# 433_RX.net
KiCad netlist of a schematic drawn in Altium Designer
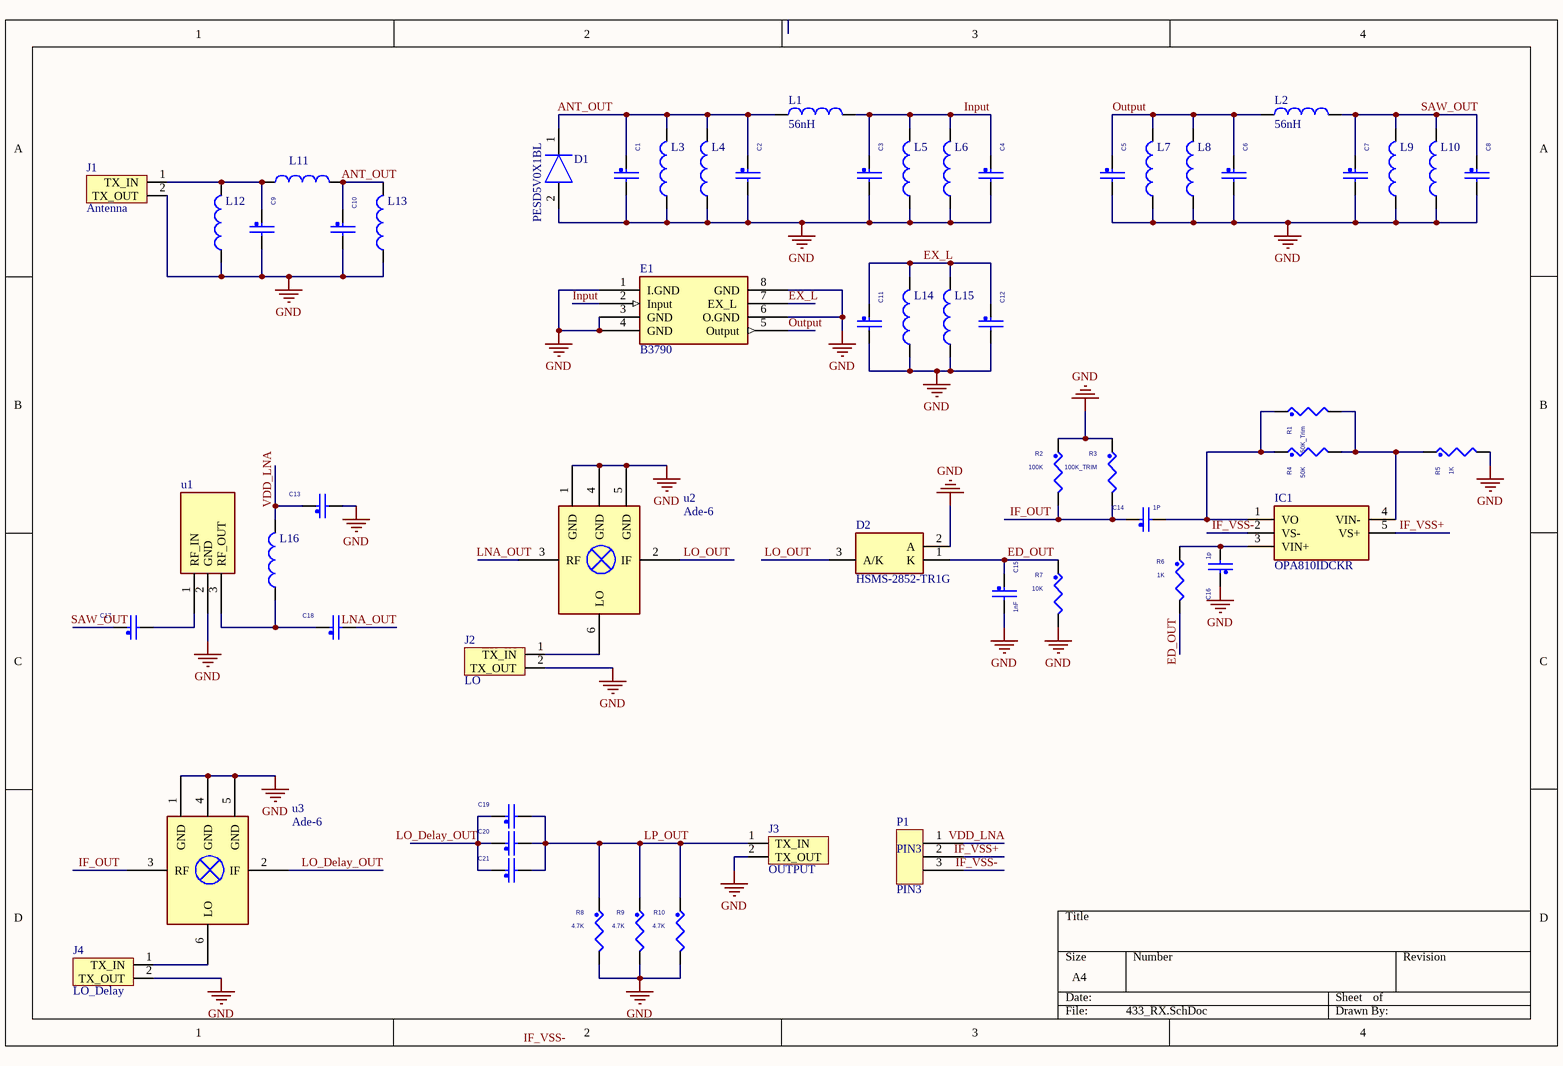
[diagram p0: 433_RX.SchDoc]

(export (version "E")
  (design (tool "Eeschema 10.0.6"))
  (components
    (comp (ref "C1")
      (value "~")
      (description "CAP CER 0.1UF 10V 10% X5R 0402")
      (fields (field (name "VOLTAGE") "10V") (field (name "TOLERANCE") "10%"))
      (libsource (lib "野火_STM32F103C8T6核心板_V1.0_原理图封装库_AD格式") (part "CAP_NP"))
    )
    (comp (ref "C2")
      (value "~")
      (description "CAP CER 0.1UF 10V 10% X5R 0402")
      (fields (field (name "VOLTAGE") "10V") (field (name "TOLERANCE") "10%"))
      (libsource (lib "野火_STM32F103C8T6核心板_V1.0_原理图封装库_AD格式") (part "CAP_NP"))
    )
    (comp (ref "C3")
      (value "~")
      (description "CAP CER 0.1UF 10V 10% X5R 0402")
      (fields (field (name "VOLTAGE") "10V") (field (name "TOLERANCE") "10%"))
      (libsource (lib "野火_STM32F103C8T6核心板_V1.0_原理图封装库_AD格式") (part "CAP_NP"))
    )
    (comp (ref "C4")
      (value "~")
      (description "CAP CER 0.1UF 10V 10% X5R 0402")
      (fields (field (name "VOLTAGE") "10V") (field (name "TOLERANCE") "10%"))
      (libsource (lib "野火_STM32F103C8T6核心板_V1.0_原理图封装库_AD格式") (part "CAP_NP"))
    )
    (comp (ref "C5")
      (value "~")
      (description "CAP CER 0.1UF 10V 10% X5R 0402")
      (fields (field (name "VOLTAGE") "10V") (field (name "TOLERANCE") "10%"))
      (libsource (lib "野火_STM32F103C8T6核心板_V1.0_原理图封装库_AD格式") (part "CAP_NP"))
    )
    (comp (ref "C6")
      (value "~")
      (description "CAP CER 0.1UF 10V 10% X5R 0402")
      (fields (field (name "VOLTAGE") "10V") (field (name "TOLERANCE") "10%"))
      (libsource (lib "野火_STM32F103C8T6核心板_V1.0_原理图封装库_AD格式") (part "CAP_NP"))
    )
    (comp (ref "C7")
      (value "~")
      (description "CAP CER 0.1UF 10V 10% X5R 0402")
      (fields (field (name "VOLTAGE") "10V") (field (name "TOLERANCE") "10%"))
      (libsource (lib "野火_STM32F103C8T6核心板_V1.0_原理图封装库_AD格式") (part "CAP_NP"))
    )
    (comp (ref "C8")
      (value "~")
      (description "CAP CER 0.1UF 10V 10% X5R 0402")
      (fields (field (name "VOLTAGE") "10V") (field (name "TOLERANCE") "10%"))
      (libsource (lib "野火_STM32F103C8T6核心板_V1.0_原理图封装库_AD格式") (part "CAP_NP"))
    )
    (comp (ref "C9")
      (value "~")
      (description "CAP CER 0.1UF 10V 10% X5R 0402")
      (fields (field (name "VOLTAGE") "10V") (field (name "TOLERANCE") "10%"))
      (libsource (lib "野火_STM32F103C8T6核心板_V1.0_原理图封装库_AD格式") (part "CAP_NP"))
    )
    (comp (ref "C10")
      (value "~")
      (description "CAP CER 0.1UF 10V 10% X5R 0402")
      (fields (field (name "VOLTAGE") "10V") (field (name "TOLERANCE") "10%"))
      (libsource (lib "野火_STM32F103C8T6核心板_V1.0_原理图封装库_AD格式") (part "CAP_NP"))
    )
    (comp (ref "C11")
      (value "~")
      (description "CAP CER 0.1UF 10V 10% X5R 0402")
      (fields (field (name "VOLTAGE") "10V") (field (name "TOLERANCE") "10%"))
      (libsource (lib "野火_STM32F103C8T6核心板_V1.0_原理图封装库_AD格式") (part "CAP_NP"))
    )
    (comp (ref "C12")
      (value "~")
      (description "CAP CER 0.1UF 10V 10% X5R 0402")
      (fields (field (name "VOLTAGE") "10V") (field (name "TOLERANCE") "10%"))
      (libsource (lib "野火_STM32F103C8T6核心板_V1.0_原理图封装库_AD格式") (part "CAP_NP"))
    )
    (comp (ref "C13")
      (value "~")
      (description "CAP CER 0.1UF 10V 10% X5R 0402")
      (fields (field (name "VOLTAGE") "10V") (field (name "TOLERANCE") "10%"))
      (libsource (lib "野火_STM32F103C8T6核心板_V1.0_原理图封装库_AD格式") (part "CAP_NP"))
    )
    (comp (ref "C14")
      (value "1P")
      (description "CAP CER 0.1UF 10V 10% X5R 0402")
      (fields (field (name "VOLTAGE") "10V") (field (name "TOLERANCE") "10%"))
      (libsource (lib "野火_STM32F103C8T6核心板_V1.0_原理图封装库_AD格式") (part "CAP_NP"))
    )
    (comp (ref "C15")
      (value "1nF")
      (description "CAP CER 0.1UF 10V 10% X5R 0402")
      (fields (field (name "VOLTAGE") "10V") (field (name "TOLERANCE") "10%"))
      (libsource (lib "野火_STM32F103C8T6核心板_V1.0_原理图封装库_AD格式") (part "CAP_NP"))
    )
    (comp (ref "C16")
      (value "1p")
      (description "CAP CER 0.1UF 10V 10% X5R 0402")
      (fields (field (name "VOLTAGE") "10V") (field (name "TOLERANCE") "10%"))
      (libsource (lib "野火_STM32F103C8T6核心板_V1.0_原理图封装库_AD格式") (part "CAP_NP"))
    )
    (comp (ref "C17")
      (value "~")
      (description "CAP CER 0.1UF 10V 10% X5R 0402")
      (fields (field (name "VOLTAGE") "10V") (field (name "TOLERANCE") "10%"))
      (libsource (lib "野火_STM32F103C8T6核心板_V1.0_原理图封装库_AD格式") (part "CAP_NP"))
    )
    (comp (ref "C18")
      (value "~")
      (description "CAP CER 0.1UF 10V 10% X5R 0402")
      (fields (field (name "VOLTAGE") "10V") (field (name "TOLERANCE") "10%"))
      (libsource (lib "野火_STM32F103C8T6核心板_V1.0_原理图封装库_AD格式") (part "CAP_NP"))
    )
    (comp (ref "C19")
      (value "~")
      (description "CAP CER 0.1UF 10V 10% X5R 0402")
      (fields (field (name "VOLTAGE") "10V") (field (name "TOLERANCE") "10%"))
      (libsource (lib "野火_STM32F103C8T6核心板_V1.0_原理图封装库_AD格式") (part "CAP_NP"))
    )
    (comp (ref "C20")
      (value "~")
      (description "CAP CER 0.1UF 10V 10% X5R 0402")
      (fields (field (name "VOLTAGE") "10V") (field (name "TOLERANCE") "10%"))
      (libsource (lib "野火_STM32F103C8T6核心板_V1.0_原理图封装库_AD格式") (part "CAP_NP"))
    )
    (comp (ref "C21")
      (value "~")
      (description "CAP CER 0.1UF 10V 10% X5R 0402")
      (fields (field (name "VOLTAGE") "10V") (field (name "TOLERANCE") "10%"))
      (libsource (lib "野火_STM32F103C8T6核心板_V1.0_原理图封装库_AD格式") (part "CAP_NP"))
    )
    (comp (ref "D1")
      (value "PESD5V0X1BL")
      (footprint "SamacSys:PESD5V0X1BL")
      (description "Diode")
      (libsource (lib "SamacSys") (part "PESD5V0X1BL"))
    )
    (comp (ref "D2")
      (value "HSMS-2852-TR1G")
      (footprint "SamacSys:SOT65P210X110-3N")
      (description "Diode")
      (fields (field (name "MOUSER PART NUMBER") "630-HSMS-2852-TR1G"))
      (libsource (lib "SamacSys") (part "HSMS-2852-TR1G"))
    )
    (comp (ref "E1") (value "B3790") (footprint "B3790") (libsource (lib "SamacSys") (part "B3790")))
    (comp (ref "IC1")
      (value "OPA810IDCKR")
      (footprint "SamacSys:SOT65P210X110-5N")
      (description "Integrated Circuit")
      (fields (field (name "MOUSER PART NUMBER") "595-OPA810IDCKR"))
      (libsource (lib "*") (part "OPA810IDCKR"))
    )
    (comp (ref "J1")
      (value "Antenna")
      (footprint "SMA-2")
      (description "SMA-2")
      (libsource (lib "SIM900_MD") (part "SMA-2"))
    )
    (comp (ref "J2")
      (value "LO")
      (footprint "SMA-2")
      (description "SMA-2")
      (libsource (lib "SIM900_MD") (part "SMA-2"))
    )
    (comp (ref "J3")
      (value "OUTPUT")
      (footprint "SMA-2")
      (description "SMA-2")
      (libsource (lib "") (part "SMA-2_1"))
    )
    (comp (ref "J4")
      (value "LO_Delay")
      (footprint "SMA-2")
      (description "SMA-2")
      (libsource (lib "SIM900_MD") (part "SMA-2"))
    )
    (comp (ref "L1")
      (value "56nH")
      (footprint "0402-A")
      (description "Inductor")
      (fields (field (name "PUBLISHER") "Altium Limited"))
      (libsource (lib "Miscellaneous Devices") (part "Inductor"))
    )
    (comp (ref "L2")
      (value "56nH")
      (footprint "0402-A")
      (description "Inductor")
      (fields (field (name "PUBLISHER") "Altium Limited"))
      (libsource (lib "Miscellaneous Devices") (part "Inductor"))
    )
    (comp (ref "L3")
      (value "~")
      (footprint "0402-A")
      (description "Inductor")
      (fields (field (name "PUBLISHER") "Altium Limited"))
      (libsource (lib "Miscellaneous Devices") (part "Inductor"))
    )
    (comp (ref "L4")
      (value "~")
      (footprint "0402-A")
      (description "Inductor")
      (fields (field (name "PUBLISHER") "Altium Limited"))
      (libsource (lib "Miscellaneous Devices") (part "Inductor"))
    )
    (comp (ref "L5")
      (value "~")
      (footprint "0402-A")
      (description "Inductor")
      (fields (field (name "PUBLISHER") "Altium Limited"))
      (libsource (lib "Miscellaneous Devices") (part "Inductor"))
    )
    (comp (ref "L6")
      (value "~")
      (footprint "0402-A")
      (description "Inductor")
      (fields (field (name "PUBLISHER") "Altium Limited"))
      (libsource (lib "Miscellaneous Devices") (part "Inductor"))
    )
    (comp (ref "L7")
      (value "~")
      (footprint "0402-A")
      (description "Inductor")
      (fields (field (name "PUBLISHER") "Altium Limited"))
      (libsource (lib "Miscellaneous Devices") (part "Inductor"))
    )
    (comp (ref "L8")
      (value "~")
      (footprint "0402-A")
      (description "Inductor")
      (fields (field (name "PUBLISHER") "Altium Limited"))
      (libsource (lib "Miscellaneous Devices") (part "Inductor"))
    )
    (comp (ref "L9")
      (value "~")
      (footprint "0402-A")
      (description "Inductor")
      (fields (field (name "PUBLISHER") "Altium Limited"))
      (libsource (lib "Miscellaneous Devices") (part "Inductor"))
    )
    (comp (ref "L10")
      (value "~")
      (footprint "0402-A")
      (description "Inductor")
      (fields (field (name "PUBLISHER") "Altium Limited"))
      (libsource (lib "Miscellaneous Devices") (part "Inductor"))
    )
    (comp (ref "L11")
      (value "56nH")
      (footprint "0402-A")
      (description "Inductor")
      (fields (field (name "PUBLISHER") "Altium Limited"))
      (libsource (lib "Miscellaneous Devices") (part "Inductor"))
    )
    (comp (ref "L12")
      (value "~")
      (footprint "0402-A")
      (description "Inductor")
      (fields (field (name "PUBLISHER") "Altium Limited"))
      (libsource (lib "Miscellaneous Devices") (part "Inductor"))
    )
    (comp (ref "L13")
      (value "~")
      (footprint "0402-A")
      (description "Inductor")
      (fields (field (name "PUBLISHER") "Altium Limited"))
      (libsource (lib "Miscellaneous Devices") (part "Inductor"))
    )
    (comp (ref "L14")
      (value "~")
      (footprint "0402-A")
      (description "Inductor")
      (fields (field (name "PUBLISHER") "Altium Limited"))
      (libsource (lib "Miscellaneous Devices") (part "Inductor"))
    )
    (comp (ref "L15")
      (value "~")
      (footprint "0402-A")
      (description "Inductor")
      (fields (field (name "PUBLISHER") "Altium Limited"))
      (libsource (lib "Miscellaneous Devices") (part "Inductor"))
    )
    (comp (ref "L16")
      (value "~")
      (footprint "0402-A")
      (description "Inductor")
      (fields (field (name "PUBLISHER") "Altium Limited"))
      (libsource (lib "Miscellaneous Devices") (part "Inductor"))
    )
    (comp (ref "P1") (value "PIN3") (footprint "PIN3") (libsource (lib "Davis_Lib") (part "PIN3")))
    (comp (ref "R1")
      (value "50K_Trim")
      (description "RES MF 1.0M 1/10W 5% 0402")
      (fields (field (name "TOLERANCE") "5%"))
      (libsource (lib "野火_STM32F103C8T6核心板_V1.0_原理图封装库_AD格式") (part "RES"))
    )
    (comp (ref "R2")
      (value "100K")
      (description "RES MF 1.0M 1/10W 5% 0402")
      (fields (field (name "TOLERANCE") "5%"))
      (libsource (lib "野火_STM32F103C8T6核心板_V1.0_原理图封装库_AD格式") (part "RES"))
    )
    (comp (ref "R3")
      (value "100K_TRIM")
      (description "RES MF 1.0M 1/10W 5% 0402")
      (fields (field (name "TOLERANCE") "5%"))
      (libsource (lib "野火_STM32F103C8T6核心板_V1.0_原理图封装库_AD格式") (part "RES"))
    )
    (comp (ref "R4")
      (value "50K")
      (description "RES MF 1.0M 1/10W 5% 0402")
      (fields (field (name "TOLERANCE") "5%"))
      (libsource (lib "野火_STM32F103C8T6核心板_V1.0_原理图封装库_AD格式") (part "RES"))
    )
    (comp (ref "R5")
      (value "1K")
      (description "RES MF 1.0M 1/10W 5% 0402")
      (fields (field (name "TOLERANCE") "5%"))
      (libsource (lib "野火_STM32F103C8T6核心板_V1.0_原理图封装库_AD格式") (part "RES"))
    )
    (comp (ref "R6")
      (value "1K")
      (description "RES MF 1.0M 1/10W 5% 0402")
      (fields (field (name "TOLERANCE") "5%"))
      (libsource (lib "野火_STM32F103C8T6核心板_V1.0_原理图封装库_AD格式") (part "RES"))
    )
    (comp (ref "R7")
      (value "10K")
      (description "RES MF 1.0M 1/10W 5% 0402")
      (fields (field (name "TOLERANCE") "5%"))
      (libsource (lib "野火_STM32F103C8T6核心板_V1.0_原理图封装库_AD格式") (part "RES"))
    )
    (comp (ref "R8")
      (value "4.7K")
      (description "RES MF 1.0M 1/10W 5% 0402")
      (fields (field (name "TOLERANCE") "5%"))
      (libsource (lib "野火_STM32F103C8T6核心板_V1.0_原理图封装库_AD格式") (part "RES"))
    )
    (comp (ref "R9")
      (value "4.7K")
      (description "RES MF 1.0M 1/10W 5% 0402")
      (fields (field (name "TOLERANCE") "5%"))
      (libsource (lib "野火_STM32F103C8T6核心板_V1.0_原理图封装库_AD格式") (part "RES"))
    )
    (comp (ref "R10")
      (value "4.7K")
      (description "RES MF 1.0M 1/10W 5% 0402")
      (fields (field (name "TOLERANCE") "5%"))
      (libsource (lib "野火_STM32F103C8T6核心板_V1.0_原理图封装库_AD格式") (part "RES"))
    )
    (comp (ref "u1") (value "1") (footprint "TOP3M9008") (libsource (lib "SamacSys") (part "TQP3M9008")))
    (comp (ref "u2") (value "Ade-6") (footprint "Ade-6") (libsource (lib "SamacSys") (part "Ade-6")))
    (comp (ref "u3") (value "Ade-6") (footprint "Ade-6") (libsource (lib "SamacSys") (part "Ade-6")))
  )
  (nets
    (net (code "1") (name "/ANT_OUT") (class "Default")
      (node (ref "C1") (pin "1") (pinfunction "1_1") (pintype "passive"))
      (node (ref "C10") (pin "1") (pinfunction "1_1") (pintype "passive"))
      (node (ref "C2") (pin "1") (pinfunction "1_1") (pintype "passive"))
      (node (ref "D1") (pin "1") (pinfunction "K_1") (pintype "passive"))
      (node (ref "L1") (pin "1") (pinfunction "1_1") (pintype "passive"))
      (node (ref "L11") (pin "2") (pinfunction "2_2") (pintype "passive"))
      (node (ref "L13") (pin "2") (pinfunction "2_2") (pintype "passive"))
      (node (ref "L3") (pin "2") (pinfunction "2_2") (pintype "passive"))
      (node (ref "L4") (pin "2") (pinfunction "2_2") (pintype "passive"))
    )
    (net (code "2") (name "/ED_OUT") (class "Default")
      (node (ref "C15") (pin "1") (pinfunction "1_1") (pintype "passive"))
      (node (ref "D2") (pin "1") (pinfunction "K_1") (pintype "passive"))
      (node (ref "R6") (pin "2") (pinfunction "2_2") (pintype "passive"))
      (node (ref "R7") (pin "1") (pinfunction "1_1") (pintype "passive"))
    )
    (net (code "3") (name "/EX_L") (class "Default")
      (node (ref "C11") (pin "1") (pinfunction "1_1") (pintype "passive"))
      (node (ref "C12") (pin "1") (pinfunction "1_1") (pintype "passive"))
      (node (ref "E1") (pin "7") (pinfunction "EX_L_7") (pintype "passive"))
      (node (ref "L14") (pin "2") (pinfunction "2_2") (pintype "passive"))
      (node (ref "L15") (pin "2") (pinfunction "2_2") (pintype "passive"))
    )
    (net (code "4") (name "/IF_OUT") (class "Default")
      (node (ref "C14") (pin "1") (pinfunction "1_1") (pintype "passive"))
      (node (ref "R2") (pin "2") (pinfunction "2_2") (pintype "passive"))
      (node (ref "R3") (pin "2") (pinfunction "2_2") (pintype "passive"))
      (node (ref "u3") (pin "3") (pinfunction "RF_3") (pintype "passive"))
    )
    (net (code "5") (name "/IF_VSS+") (class "Default")
      (node (ref "IC1") (pin "5") (pinfunction "VS+_5") (pintype "passive"))
      (node (ref "P1") (pin "2") (pinfunction "2_2") (pintype "passive"))
    )
    (net (code "6") (name "/IF_VSS-") (class "Default")
      (node (ref "IC1") (pin "2") (pinfunction "VS-_2") (pintype "passive"))
      (node (ref "P1") (pin "3") (pinfunction "3_3") (pintype "passive"))
    )
    (net (code "7") (name "/Input") (class "Default")
      (node (ref "C3") (pin "1") (pinfunction "1_1") (pintype "passive"))
      (node (ref "C4") (pin "1") (pinfunction "1_1") (pintype "passive"))
      (node (ref "E1") (pin "2") (pinfunction "Input_2") (pintype "input"))
      (node (ref "L1") (pin "2") (pinfunction "2_2") (pintype "passive"))
      (node (ref "L5") (pin "2") (pinfunction "2_2") (pintype "passive"))
      (node (ref "L6") (pin "2") (pinfunction "2_2") (pintype "passive"))
    )
    (net (code "8") (name "/LNA_OUT") (class "Default")
      (node (ref "C18") (pin "2") (pinfunction "2_2") (pintype "passive"))
      (node (ref "u2") (pin "3") (pinfunction "RF_3") (pintype "passive"))
    )
    (net (code "9") (name "/LO_Delay_OUT") (class "Default")
      (node (ref "C19") (pin "1") (pinfunction "1_1") (pintype "passive"))
      (node (ref "C20") (pin "1") (pinfunction "1_1") (pintype "passive"))
      (node (ref "C21") (pin "1") (pinfunction "1_1") (pintype "passive"))
      (node (ref "u3") (pin "2") (pinfunction "IF_2") (pintype "passive"))
    )
    (net (code "10") (name "/LO_OUT") (class "Default")
      (node (ref "D2") (pin "3") (pinfunction "A/K_3") (pintype "passive"))
      (node (ref "u2") (pin "2") (pinfunction "IF_2") (pintype "passive"))
    )
    (net (code "11") (name "/LP_OUT") (class "Default")
      (node (ref "C19") (pin "2") (pinfunction "2_2") (pintype "passive"))
      (node (ref "C20") (pin "2") (pinfunction "2_2") (pintype "passive"))
      (node (ref "C21") (pin "2") (pinfunction "2_2") (pintype "passive"))
      (node (ref "J3") (pin "1") (pinfunction "TX_IN_1") (pintype "passive"))
      (node (ref "R10") (pin "1") (pinfunction "1_1") (pintype "passive"))
      (node (ref "R8") (pin "1") (pinfunction "1_1") (pintype "passive"))
      (node (ref "R9") (pin "1") (pinfunction "1_1") (pintype "passive"))
    )
    (net (code "12") (name "/Output") (class "Default")
      (node (ref "C5") (pin "1") (pinfunction "1_1") (pintype "passive"))
      (node (ref "C6") (pin "1") (pinfunction "1_1") (pintype "passive"))
      (node (ref "E1") (pin "5") (pinfunction "Output_5") (pintype "output"))
      (node (ref "L2") (pin "1") (pinfunction "1_1") (pintype "passive"))
      (node (ref "L7") (pin "2") (pinfunction "2_2") (pintype "passive"))
      (node (ref "L8") (pin "2") (pinfunction "2_2") (pintype "passive"))
    )
    (net (code "13") (name "/SAW_OUT") (class "Default")
      (node (ref "C17") (pin "1") (pinfunction "1_1") (pintype "passive"))
      (node (ref "C7") (pin "1") (pinfunction "1_1") (pintype "passive"))
      (node (ref "C8") (pin "1") (pinfunction "1_1") (pintype "passive"))
      (node (ref "L10") (pin "2") (pinfunction "2_2") (pintype "passive"))
      (node (ref "L2") (pin "2") (pinfunction "2_2") (pintype "passive"))
      (node (ref "L9") (pin "2") (pinfunction "2_2") (pintype "passive"))
    )
    (net (code "14") (name "/VDD_LNA") (class "Default")
      (node (ref "C13") (pin "1") (pinfunction "1_1") (pintype "passive"))
      (node (ref "L16") (pin "2") (pinfunction "2_2") (pintype "passive"))
      (node (ref "P1") (pin "1") (pinfunction "1_1") (pintype "passive"))
    )
    (net (code "15") (name "GND") (class "Default")
      (node (ref "C1") (pin "2") (pinfunction "2_2") (pintype "passive"))
      (node (ref "C10") (pin "2") (pinfunction "2_2") (pintype "passive"))
      (node (ref "C11") (pin "2") (pinfunction "2_2") (pintype "passive"))
      (node (ref "C12") (pin "2") (pinfunction "2_2") (pintype "passive"))
      (node (ref "C13") (pin "2") (pinfunction "2_2") (pintype "passive"))
      (node (ref "C15") (pin "2") (pinfunction "2_2") (pintype "passive"))
      (node (ref "C16") (pin "1") (pinfunction "1_1") (pintype "passive"))
      (node (ref "C2") (pin "2") (pinfunction "2_2") (pintype "passive"))
      (node (ref "C3") (pin "2") (pinfunction "2_2") (pintype "passive"))
      (node (ref "C4") (pin "2") (pinfunction "2_2") (pintype "passive"))
      (node (ref "C5") (pin "2") (pinfunction "2_2") (pintype "passive"))
      (node (ref "C6") (pin "2") (pinfunction "2_2") (pintype "passive"))
      (node (ref "C7") (pin "2") (pinfunction "2_2") (pintype "passive"))
      (node (ref "C8") (pin "2") (pinfunction "2_2") (pintype "passive"))
      (node (ref "C9") (pin "2") (pinfunction "2_2") (pintype "passive"))
      (node (ref "D1") (pin "2") (pinfunction "A_2") (pintype "passive"))
      (node (ref "D2") (pin "2") (pinfunction "A_2") (pintype "passive"))
      (node (ref "E1") (pin "1") (pinfunction "I.GND_1") (pintype "power_in"))
      (node (ref "E1") (pin "3") (pinfunction "GND_3") (pintype "power_in"))
      (node (ref "E1") (pin "4") (pinfunction "GND_4") (pintype "passive"))
      (node (ref "E1") (pin "6") (pinfunction "O.GND_6") (pintype "power_in"))
      (node (ref "E1") (pin "8") (pinfunction "GND_8") (pintype "passive"))
      (node (ref "J1") (pin "2") (pinfunction "TX_OUT_2") (pintype "passive"))
      (node (ref "J2") (pin "2") (pinfunction "TX_OUT_2") (pintype "passive"))
      (node (ref "J3") (pin "2") (pinfunction "TX_OUT_2") (pintype "passive"))
      (node (ref "J4") (pin "2") (pinfunction "TX_OUT_2") (pintype "passive"))
      (node (ref "L10") (pin "1") (pinfunction "1_1") (pintype "passive"))
      (node (ref "L12") (pin "1") (pinfunction "1_1") (pintype "passive"))
      (node (ref "L13") (pin "1") (pinfunction "1_1") (pintype "passive"))
      (node (ref "L14") (pin "1") (pinfunction "1_1") (pintype "passive"))
      (node (ref "L15") (pin "1") (pinfunction "1_1") (pintype "passive"))
      (node (ref "L3") (pin "1") (pinfunction "1_1") (pintype "passive"))
      (node (ref "L4") (pin "1") (pinfunction "1_1") (pintype "passive"))
      (node (ref "L5") (pin "1") (pinfunction "1_1") (pintype "passive"))
      (node (ref "L6") (pin "1") (pinfunction "1_1") (pintype "passive"))
      (node (ref "L7") (pin "1") (pinfunction "1_1") (pintype "passive"))
      (node (ref "L8") (pin "1") (pinfunction "1_1") (pintype "passive"))
      (node (ref "L9") (pin "1") (pinfunction "1_1") (pintype "passive"))
      (node (ref "R10") (pin "2") (pinfunction "2_2") (pintype "passive"))
      (node (ref "R2") (pin "1") (pinfunction "1_1") (pintype "passive"))
      (node (ref "R3") (pin "1") (pinfunction "1_1") (pintype "passive"))
      (node (ref "R5") (pin "2") (pinfunction "2_2") (pintype "passive"))
      (node (ref "R7") (pin "2") (pinfunction "2_2") (pintype "passive"))
      (node (ref "R8") (pin "2") (pinfunction "2_2") (pintype "passive"))
      (node (ref "R9") (pin "2") (pinfunction "2_2") (pintype "passive"))
      (node (ref "u1") (pin "2") (pinfunction "GND_2") (pintype "passive"))
      (node (ref "u2") (pin "1") (pinfunction "GND_1") (pintype "passive"))
      (node (ref "u2") (pin "4") (pinfunction "GND_4") (pintype "passive"))
      (node (ref "u2") (pin "5") (pinfunction "GND_5") (pintype "passive"))
      (node (ref "u3") (pin "1") (pinfunction "GND_1") (pintype "passive"))
      (node (ref "u3") (pin "4") (pinfunction "GND_4") (pintype "passive"))
      (node (ref "u3") (pin "5") (pinfunction "GND_5") (pintype "passive"))
    )
    (net (code "16") (name "Net-(IC1-VIN+)") (class "Default")
      (node (ref "C16") (pin "2") (pinfunction "2_2") (pintype "passive"))
      (node (ref "IC1") (pin "3") (pinfunction "VIN+_3") (pintype "passive"))
      (node (ref "R6") (pin "1") (pinfunction "1_1") (pintype "passive"))
    )
    (net (code "17") (name "Net-(IC1-VIN-)") (class "Default")
      (node (ref "IC1") (pin "4") (pinfunction "VIN-_4") (pintype "passive"))
      (node (ref "R1") (pin "2") (pinfunction "2_2") (pintype "passive"))
      (node (ref "R4") (pin "2") (pinfunction "2_2") (pintype "passive"))
      (node (ref "R5") (pin "1") (pinfunction "1_1") (pintype "passive"))
    )
    (net (code "18") (name "Net-(IC1-VO)") (class "Default")
      (node (ref "C14") (pin "2") (pinfunction "2_2") (pintype "passive"))
      (node (ref "IC1") (pin "1") (pinfunction "VO_1") (pintype "passive"))
      (node (ref "R1") (pin "1") (pinfunction "1_1") (pintype "passive"))
      (node (ref "R4") (pin "1") (pinfunction "1_1") (pintype "passive"))
    )
    (net (code "19") (name "Net-(J1-TX_IN)") (class "Default")
      (node (ref "C9") (pin "1") (pinfunction "1_1") (pintype "passive"))
      (node (ref "J1") (pin "1") (pinfunction "TX_IN_1") (pintype "passive"))
      (node (ref "L11") (pin "1") (pinfunction "1_1") (pintype "passive"))
      (node (ref "L12") (pin "2") (pinfunction "2_2") (pintype "passive"))
    )
    (net (code "20") (name "Net-(J2-TX_IN)") (class "Default")
      (node (ref "J2") (pin "1") (pinfunction "TX_IN_1") (pintype "passive"))
      (node (ref "u2") (pin "6") (pinfunction "LO_6") (pintype "passive"))
    )
    (net (code "21") (name "Net-(J4-TX_IN)") (class "Default")
      (node (ref "J4") (pin "1") (pinfunction "TX_IN_1") (pintype "passive"))
      (node (ref "u3") (pin "6") (pinfunction "LO_6") (pintype "passive"))
    )
    (net (code "22") (name "Net-(u1-RF_IN)") (class "Default")
      (node (ref "C17") (pin "2") (pinfunction "2_2") (pintype "passive"))
      (node (ref "u1") (pin "1") (pinfunction "RF_IN_1") (pintype "passive"))
    )
    (net (code "23") (name "Net-(u1-RF_OUT)") (class "Default")
      (node (ref "C18") (pin "1") (pinfunction "1_1") (pintype "passive"))
      (node (ref "L16") (pin "1") (pinfunction "1_1") (pintype "passive"))
      (node (ref "u1") (pin "3") (pinfunction "RF_OUT_3") (pintype "passive"))
    )
  )
)
